# dongle.net
KiCad netlist of a schematic drawn in EAGLE
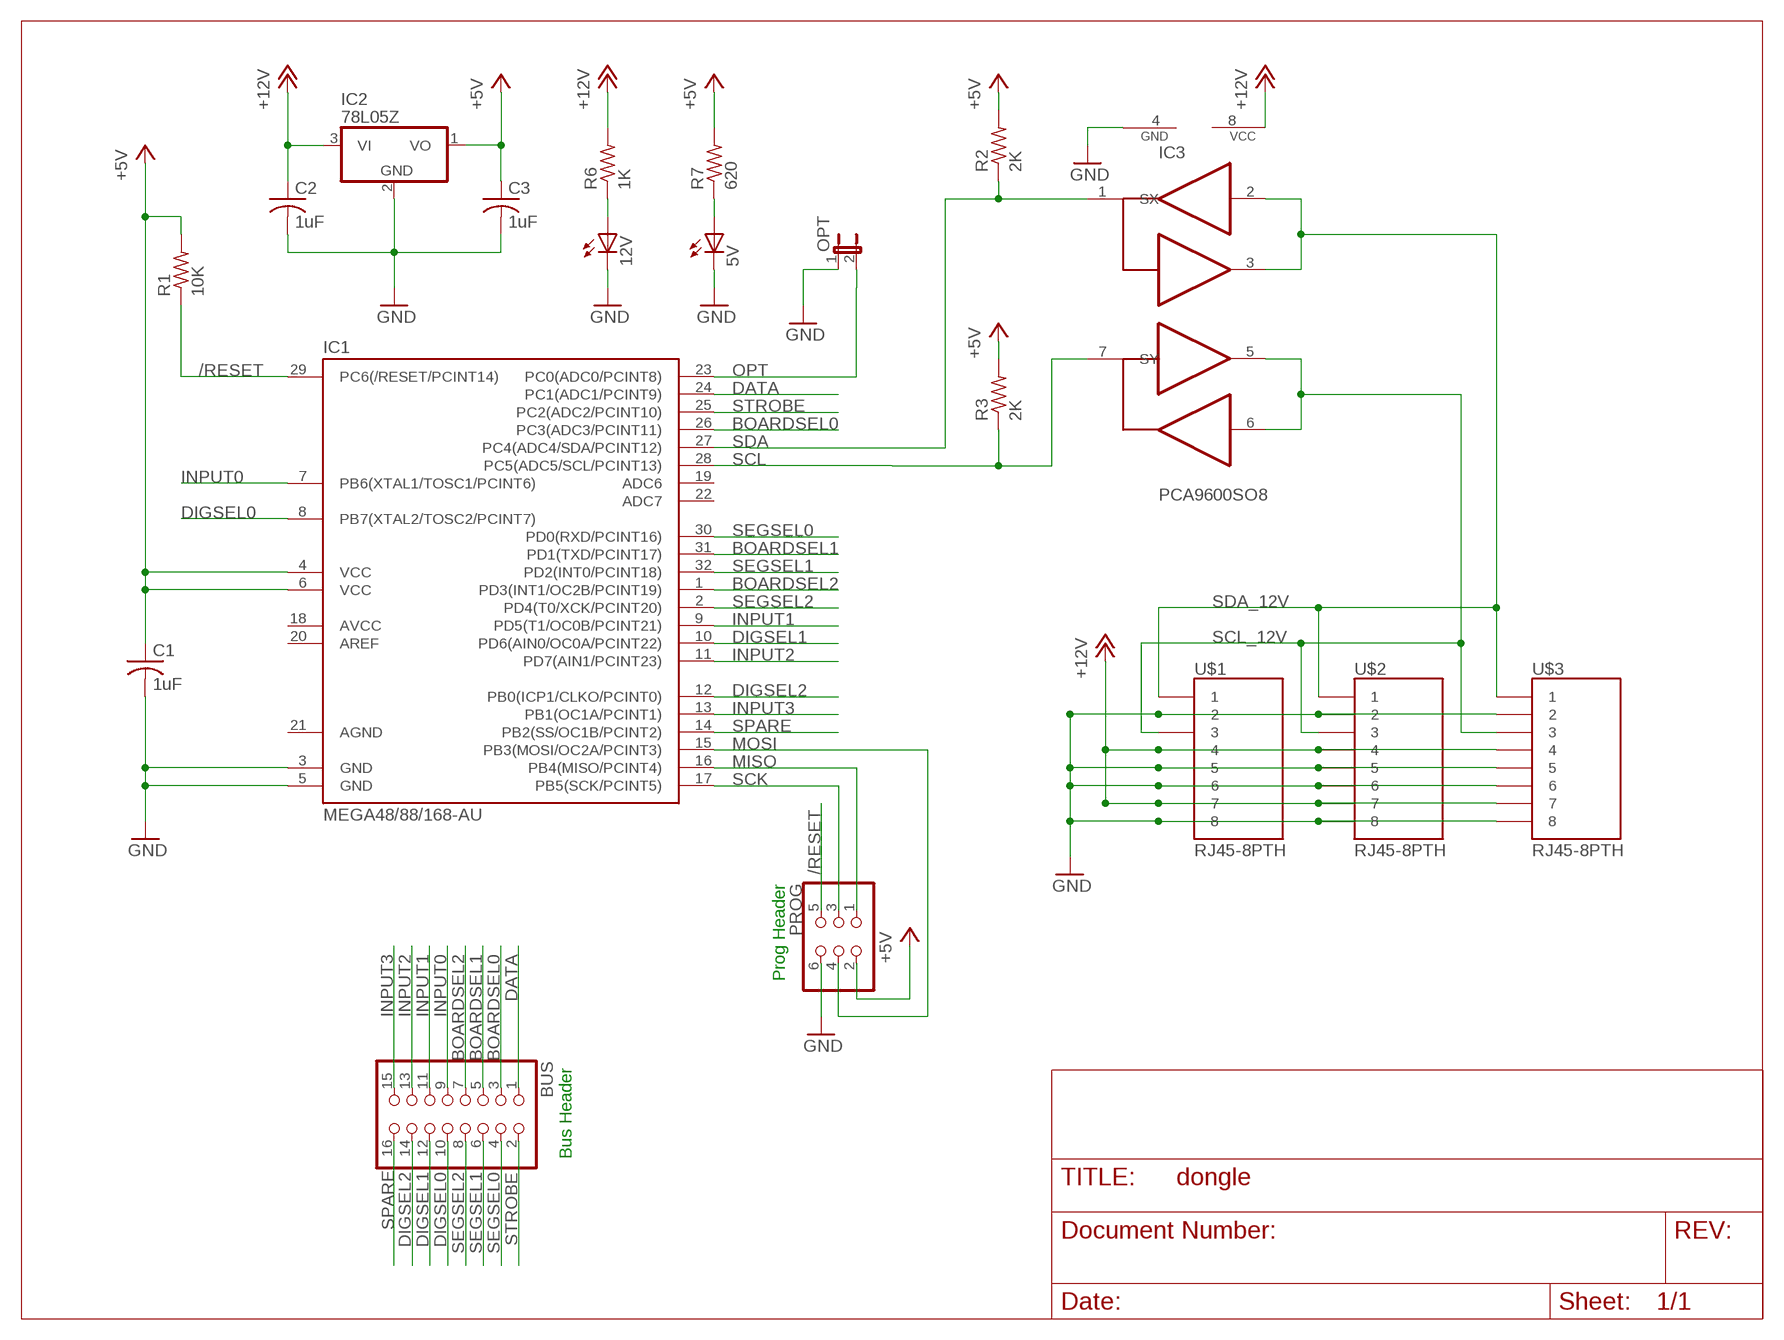
[diagram p0: schematic, sheet 1]

(export (version "E")
  (design (tool "Eeschema 10.0.6"))
  (components
    (comp (ref "5V")
      (value "LED3MM")
      (footprint "eagle-import:LED3MM")
      (libsource (lib "eagle-import") (part "LED3MM"))
    )
    (comp (ref "12V")
      (value "LED3MM")
      (footprint "eagle-import:LED3MM")
      (libsource (lib "eagle-import") (part "LED3MM"))
    )
    (comp (ref "BUS")
      (value "PINHD-2X8")
      (footprint "eagle-import:2X08")
      (libsource (lib "eagle-import") (part "PINHD-2X8"))
    )
    (comp (ref "C1")
      (value "1uF")
      (footprint "eagle-import:C025-025X050")
      (libsource (lib "eagle-import") (part "C-US025-025X050"))
    )
    (comp (ref "C2")
      (value "1uF")
      (footprint "eagle-import:C025-025X050")
      (libsource (lib "eagle-import") (part "C-US025-025X050"))
    )
    (comp (ref "C3")
      (value "1uF")
      (footprint "eagle-import:C025-025X050")
      (libsource (lib "eagle-import") (part "C-US025-025X050"))
    )
    (comp (ref "IC1")
      (value "MEGA48/88/168-AU")
      (footprint "eagle-import:TQFP32-08")
      (libsource (lib "eagle-import") (part "MEGA48/88/168-AU"))
    )
    (comp (ref "IC2")
      (value "78L05Z")
      (footprint "eagle-import:TO92")
      (libsource (lib "eagle-import") (part "78ZL05"))
    )
    (comp (ref "IC3")
      (value "PCA9600SO8")
      (footprint "eagle-import:SO08")
      (libsource (lib "eagle-import") (part "PCA9600SO8"))
    )
    (comp (ref "OPT")
      (value "JUMPER-2PTH")
      (footprint "eagle-import:1X02")
      (libsource (lib "eagle-import") (part "JUMPER-2PTH"))
    )
    (comp (ref "PROG")
      (value "PINHD-2X3")
      (footprint "eagle-import:2X03")
      (libsource (lib "eagle-import") (part "PINHD-2X3"))
    )
    (comp (ref "R1")
      (value "10K")
      (footprint "eagle-import:0204_5")
      (libsource (lib "eagle-import") (part "R-US_0204/5"))
    )
    (comp (ref "R2")
      (value "2K")
      (footprint "eagle-import:0204_5")
      (libsource (lib "eagle-import") (part "R-US_0204/5"))
    )
    (comp (ref "R3")
      (value "2K")
      (footprint "eagle-import:0204_5")
      (libsource (lib "eagle-import") (part "R-US_0204/5"))
    )
    (comp (ref "R6")
      (value "1K")
      (footprint "eagle-import:0204_5")
      (libsource (lib "eagle-import") (part "R-US_0204/5"))
    )
    (comp (ref "R7")
      (value "620")
      (footprint "eagle-import:0204_5")
      (libsource (lib "eagle-import") (part "R-US_0204/5"))
    )
    (comp (ref "U$1")
      (value "RJ45-8PTH")
      (footprint "eagle-import:RJ45-8")
      (libsource (lib "eagle-import") (part "RJ45-8PTH"))
    )
    (comp (ref "U$2")
      (value "RJ45-8PTH")
      (footprint "eagle-import:RJ45-8")
      (libsource (lib "eagle-import") (part "RJ45-8PTH"))
    )
    (comp (ref "U$3")
      (value "RJ45-8PTH")
      (footprint "eagle-import:RJ45-8")
      (libsource (lib "eagle-import") (part "RJ45-8PTH"))
    )
  )
  (nets
    (net (code "1") (name "+5V") (class "Default")
      (node (ref "C1") (pin "1") (pinfunction "1_1") (pintype "passive"))
      (node (ref "C3") (pin "1") (pinfunction "1_1") (pintype "passive"))
      (node (ref "IC1") (pin "4") (pinfunction "VCC_4") (pintype "power_in"))
      (node (ref "IC1") (pin "6") (pinfunction "VCC_6") (pintype "power_in"))
      (node (ref "IC2") (pin "1") (pinfunction "VO_1") (pintype "passive"))
      (node (ref "PROG") (pin "2") (pinfunction "2_2") (pintype "passive"))
      (node (ref "R1") (pin "2") (pinfunction "2_2") (pintype "passive"))
      (node (ref "R2") (pin "2") (pinfunction "2_2") (pintype "passive"))
      (node (ref "R3") (pin "2") (pinfunction "2_2") (pintype "passive"))
      (node (ref "R7") (pin "2") (pinfunction "2_2") (pintype "passive"))
    )
    (net (code "2") (name "+12V") (class "Default")
      (node (ref "C2") (pin "1") (pinfunction "1_1") (pintype "passive"))
      (node (ref "IC2") (pin "3") (pinfunction "VI_3") (pintype "input"))
      (node (ref "IC3") (pin "8") (pinfunction "VCC_8") (pintype "power_in"))
      (node (ref "R6") (pin "2") (pinfunction "2_2") (pintype "passive"))
      (node (ref "U$1") (pin "4") (pinfunction "4_4") (pintype "bidirectional"))
      (node (ref "U$1") (pin "7") (pinfunction "7_7") (pintype "bidirectional"))
      (node (ref "U$2") (pin "4") (pinfunction "4_4") (pintype "bidirectional"))
      (node (ref "U$2") (pin "7") (pinfunction "7_7") (pintype "bidirectional"))
      (node (ref "U$3") (pin "4") (pinfunction "4_4") (pintype "bidirectional"))
      (node (ref "U$3") (pin "7") (pinfunction "7_7") (pintype "bidirectional"))
    )
    (net (code "3") (name "/AGND") (class "Default")
      (node (ref "IC1") (pin "21") (pinfunction "AGND_21") (pintype "power_in"))
    )
    (net (code "4") (name "/BOARDSEL0") (class "Default")
      (node (ref "BUS") (pin "3") (pinfunction "3_3") (pintype "passive"))
      (node (ref "IC1") (pin "26") (pinfunction "PC3(ADC3/PCINT11)_26") (pintype "bidirectional"))
    )
    (net (code "5") (name "/BOARDSEL1") (class "Default")
      (node (ref "BUS") (pin "5") (pinfunction "5_5") (pintype "passive"))
      (node (ref "IC1") (pin "31") (pinfunction "PD1(TXD/PCINT17)_31") (pintype "bidirectional"))
    )
    (net (code "6") (name "/BOARDSEL2") (class "Default")
      (node (ref "BUS") (pin "7") (pinfunction "7_7") (pintype "passive"))
      (node (ref "IC1") (pin "1") (pinfunction "PD3(INT1/OC2B/PCINT19)_1") (pintype "bidirectional"))
    )
    (net (code "7") (name "/DATA") (class "Default")
      (node (ref "BUS") (pin "1") (pinfunction "1_1") (pintype "passive"))
      (node (ref "IC1") (pin "24") (pinfunction "PC1(ADC1/PCINT9)_24") (pintype "bidirectional"))
    )
    (net (code "8") (name "/DIGSEL0") (class "Default")
      (node (ref "BUS") (pin "10") (pinfunction "10_10") (pintype "passive"))
      (node (ref "IC1") (pin "8") (pinfunction "PB7(XTAL2/TOSC2/PCINT7)_8") (pintype "bidirectional"))
    )
    (net (code "9") (name "/DIGSEL1") (class "Default")
      (node (ref "BUS") (pin "12") (pinfunction "12_12") (pintype "passive"))
      (node (ref "IC1") (pin "10") (pinfunction "PD6(AIN0/OC0A/PCINT22)_10") (pintype "bidirectional"))
    )
    (net (code "10") (name "/DIGSEL2") (class "Default")
      (node (ref "BUS") (pin "14") (pinfunction "14_14") (pintype "passive"))
      (node (ref "IC1") (pin "12") (pinfunction "PB0(ICP1/CLKO/PCINT0)_12") (pintype "bidirectional"))
    )
    (net (code "11") (name "/INPUT0") (class "Default")
      (node (ref "BUS") (pin "9") (pinfunction "9_9") (pintype "passive"))
      (node (ref "IC1") (pin "7") (pinfunction "PB6(XTAL1/TOSC1/PCINT6)_7") (pintype "bidirectional"))
    )
    (net (code "12") (name "/INPUT1") (class "Default")
      (node (ref "BUS") (pin "11") (pinfunction "11_11") (pintype "passive"))
      (node (ref "IC1") (pin "9") (pinfunction "PD5(T1/OC0B/PCINT21)_9") (pintype "bidirectional"))
    )
    (net (code "13") (name "/INPUT2") (class "Default")
      (node (ref "BUS") (pin "13") (pinfunction "13_13") (pintype "passive"))
      (node (ref "IC1") (pin "11") (pinfunction "PD7(AIN1/PCINT23)_11") (pintype "bidirectional"))
    )
    (net (code "14") (name "/INPUT3") (class "Default")
      (node (ref "BUS") (pin "15") (pinfunction "15_15") (pintype "passive"))
      (node (ref "IC1") (pin "13") (pinfunction "PB1(OC1A/PCINT1)_13") (pintype "bidirectional"))
    )
    (net (code "15") (name "/MISO") (class "Default")
      (node (ref "IC1") (pin "16") (pinfunction "PB4(MISO/PCINT4)_16") (pintype "bidirectional"))
      (node (ref "PROG") (pin "1") (pinfunction "1_1") (pintype "passive"))
    )
    (net (code "16") (name "/MOSI") (class "Default")
      (node (ref "IC1") (pin "15") (pinfunction "PB3(MOSI/OC2A/PCINT3)_15") (pintype "bidirectional"))
      (node (ref "PROG") (pin "4") (pinfunction "4_4") (pintype "passive"))
    )
    (net (code "17") (name "/OPT") (class "Default")
      (node (ref "IC1") (pin "23") (pinfunction "PC0(ADC0/PCINT8)_23") (pintype "bidirectional"))
      (node (ref "OPT") (pin "2") (pinfunction "2_2") (pintype "passive"))
    )
    (net (code "18") (name "/SCK") (class "Default")
      (node (ref "IC1") (pin "17") (pinfunction "PB5(SCK/PCINT5)_17") (pintype "bidirectional"))
      (node (ref "PROG") (pin "3") (pinfunction "3_3") (pintype "passive"))
    )
    (net (code "19") (name "/SCL") (class "Default")
      (node (ref "IC1") (pin "28") (pinfunction "PC5(ADC5/SCL/PCINT13)_28") (pintype "bidirectional"))
      (node (ref "IC3") (pin "7") (pinfunction "SY_7") (pintype "bidirectional"))
      (node (ref "R3") (pin "1") (pinfunction "1_1") (pintype "passive"))
    )
    (net (code "20") (name "/SCL_12V") (class "Default")
      (node (ref "IC3") (pin "5") (pinfunction "TY_5") (pintype "output"))
      (node (ref "IC3") (pin "6") (pinfunction "RY_6") (pintype "input"))
      (node (ref "U$1") (pin "3") (pinfunction "3_3") (pintype "bidirectional"))
      (node (ref "U$2") (pin "3") (pinfunction "3_3") (pintype "bidirectional"))
      (node (ref "U$3") (pin "3") (pinfunction "3_3") (pintype "bidirectional"))
    )
    (net (code "21") (name "/SDA") (class "Default")
      (node (ref "IC1") (pin "27") (pinfunction "PC4(ADC4/SDA/PCINT12)_27") (pintype "bidirectional"))
      (node (ref "IC3") (pin "1") (pinfunction "SX_1") (pintype "bidirectional"))
      (node (ref "R2") (pin "1") (pinfunction "1_1") (pintype "passive"))
    )
    (net (code "22") (name "/SDA_12V") (class "Default")
      (node (ref "IC3") (pin "2") (pinfunction "RX_2") (pintype "input"))
      (node (ref "IC3") (pin "3") (pinfunction "TX_3") (pintype "output"))
      (node (ref "U$1") (pin "1") (pinfunction "1_1") (pintype "bidirectional"))
      (node (ref "U$2") (pin "1") (pinfunction "1_1") (pintype "bidirectional"))
      (node (ref "U$3") (pin "1") (pinfunction "1_1") (pintype "bidirectional"))
    )
    (net (code "23") (name "/SEGSEL0") (class "Default")
      (node (ref "BUS") (pin "4") (pinfunction "4_4") (pintype "passive"))
      (node (ref "IC1") (pin "30") (pinfunction "PD0(RXD/PCINT16)_30") (pintype "bidirectional"))
    )
    (net (code "24") (name "/SEGSEL1") (class "Default")
      (node (ref "BUS") (pin "6") (pinfunction "6_6") (pintype "passive"))
      (node (ref "IC1") (pin "32") (pinfunction "PD2(INT0/PCINT18)_32") (pintype "bidirectional"))
    )
    (net (code "25") (name "/SEGSEL2") (class "Default")
      (node (ref "BUS") (pin "8") (pinfunction "8_8") (pintype "passive"))
      (node (ref "IC1") (pin "2") (pinfunction "PD4(T0/XCK/PCINT20)_2") (pintype "bidirectional"))
    )
    (net (code "26") (name "/SPARE") (class "Default")
      (node (ref "BUS") (pin "16") (pinfunction "16_16") (pintype "passive"))
      (node (ref "IC1") (pin "14") (pinfunction "PB2(SS/OC1B/PCINT2)_14") (pintype "bidirectional"))
    )
    (net (code "27") (name "/STROBE") (class "Default")
      (node (ref "BUS") (pin "2") (pinfunction "2_2") (pintype "passive"))
      (node (ref "IC1") (pin "25") (pinfunction "PC2(ADC2/PCINT10)_25") (pintype "bidirectional"))
    )
    (net (code "28") (name "/{slash}RESET") (class "Default")
      (node (ref "IC1") (pin "29") (pinfunction "PC6(/RESET/PCINT14)_29") (pintype "bidirectional"))
      (node (ref "PROG") (pin "5") (pinfunction "5_5") (pintype "passive"))
      (node (ref "R1") (pin "1") (pinfunction "1_1") (pintype "passive"))
    )
    (net (code "29") (name "GND") (class "Default")
      (node (ref "12V") (pin "K") (pinfunction "C_K") (pintype "passive"))
      (node (ref "5V") (pin "K") (pinfunction "C_K") (pintype "passive"))
      (node (ref "C1") (pin "2") (pinfunction "2_2") (pintype "passive"))
      (node (ref "C2") (pin "2") (pinfunction "2_2") (pintype "passive"))
      (node (ref "C3") (pin "2") (pinfunction "2_2") (pintype "passive"))
      (node (ref "IC1") (pin "3") (pinfunction "GND_3") (pintype "power_in"))
      (node (ref "IC1") (pin "5") (pinfunction "GND_5") (pintype "power_in"))
      (node (ref "IC2") (pin "2") (pinfunction "GND_2") (pintype "passive"))
      (node (ref "IC3") (pin "4") (pinfunction "GND_4") (pintype "power_in"))
      (node (ref "OPT") (pin "1") (pinfunction "1_1") (pintype "passive"))
      (node (ref "PROG") (pin "6") (pinfunction "6_6") (pintype "passive"))
      (node (ref "U$1") (pin "2") (pinfunction "2_2") (pintype "bidirectional"))
      (node (ref "U$1") (pin "5") (pinfunction "5_5") (pintype "bidirectional"))
      (node (ref "U$1") (pin "6") (pinfunction "6_6") (pintype "bidirectional"))
      (node (ref "U$1") (pin "8") (pinfunction "8_8") (pintype "bidirectional"))
      (node (ref "U$2") (pin "2") (pinfunction "2_2") (pintype "bidirectional"))
      (node (ref "U$2") (pin "5") (pinfunction "5_5") (pintype "bidirectional"))
      (node (ref "U$2") (pin "6") (pinfunction "6_6") (pintype "bidirectional"))
      (node (ref "U$2") (pin "8") (pinfunction "8_8") (pintype "bidirectional"))
      (node (ref "U$3") (pin "2") (pinfunction "2_2") (pintype "bidirectional"))
      (node (ref "U$3") (pin "5") (pinfunction "5_5") (pintype "bidirectional"))
      (node (ref "U$3") (pin "6") (pinfunction "6_6") (pintype "bidirectional"))
      (node (ref "U$3") (pin "8") (pinfunction "8_8") (pintype "bidirectional"))
    )
    (net (code "30") (name "Net-(5V-PadA)") (class "Default")
      (node (ref "5V") (pin "A") (pinfunction "A_A") (pintype "passive"))
      (node (ref "R7") (pin "1") (pinfunction "1_1") (pintype "passive"))
    )
    (net (code "31") (name "Net-(12V-PadA)") (class "Default")
      (node (ref "12V") (pin "A") (pinfunction "A_A") (pintype "passive"))
      (node (ref "R6") (pin "1") (pinfunction "1_1") (pintype "passive"))
    )
    (net (code "32") (name "unconnected-(IC1-ADC6-Pad19)") (class "Default")
      (node (ref "IC1") (pin "19") (pinfunction "ADC6_19") (pintype "passive"))
    )
    (net (code "33") (name "unconnected-(IC1-ADC7-Pad22)") (class "Default")
      (node (ref "IC1") (pin "22") (pinfunction "ADC7_22") (pintype "passive"))
    )
    (net (code "34") (name "unconnected-(IC1-AREF-Pad20)") (class "Default")
      (node (ref "IC1") (pin "20") (pinfunction "AREF_20") (pintype "passive"))
    )
    (net (code "35") (name "unconnected-(IC1-AVCC-Pad18)") (class "Default")
      (node (ref "IC1") (pin "18") (pinfunction "AVCC_18") (pintype "passive"))
    )
  )
)
